# MethaneFlux.net
KiCad netlist of a schematic drawn in EAGLE
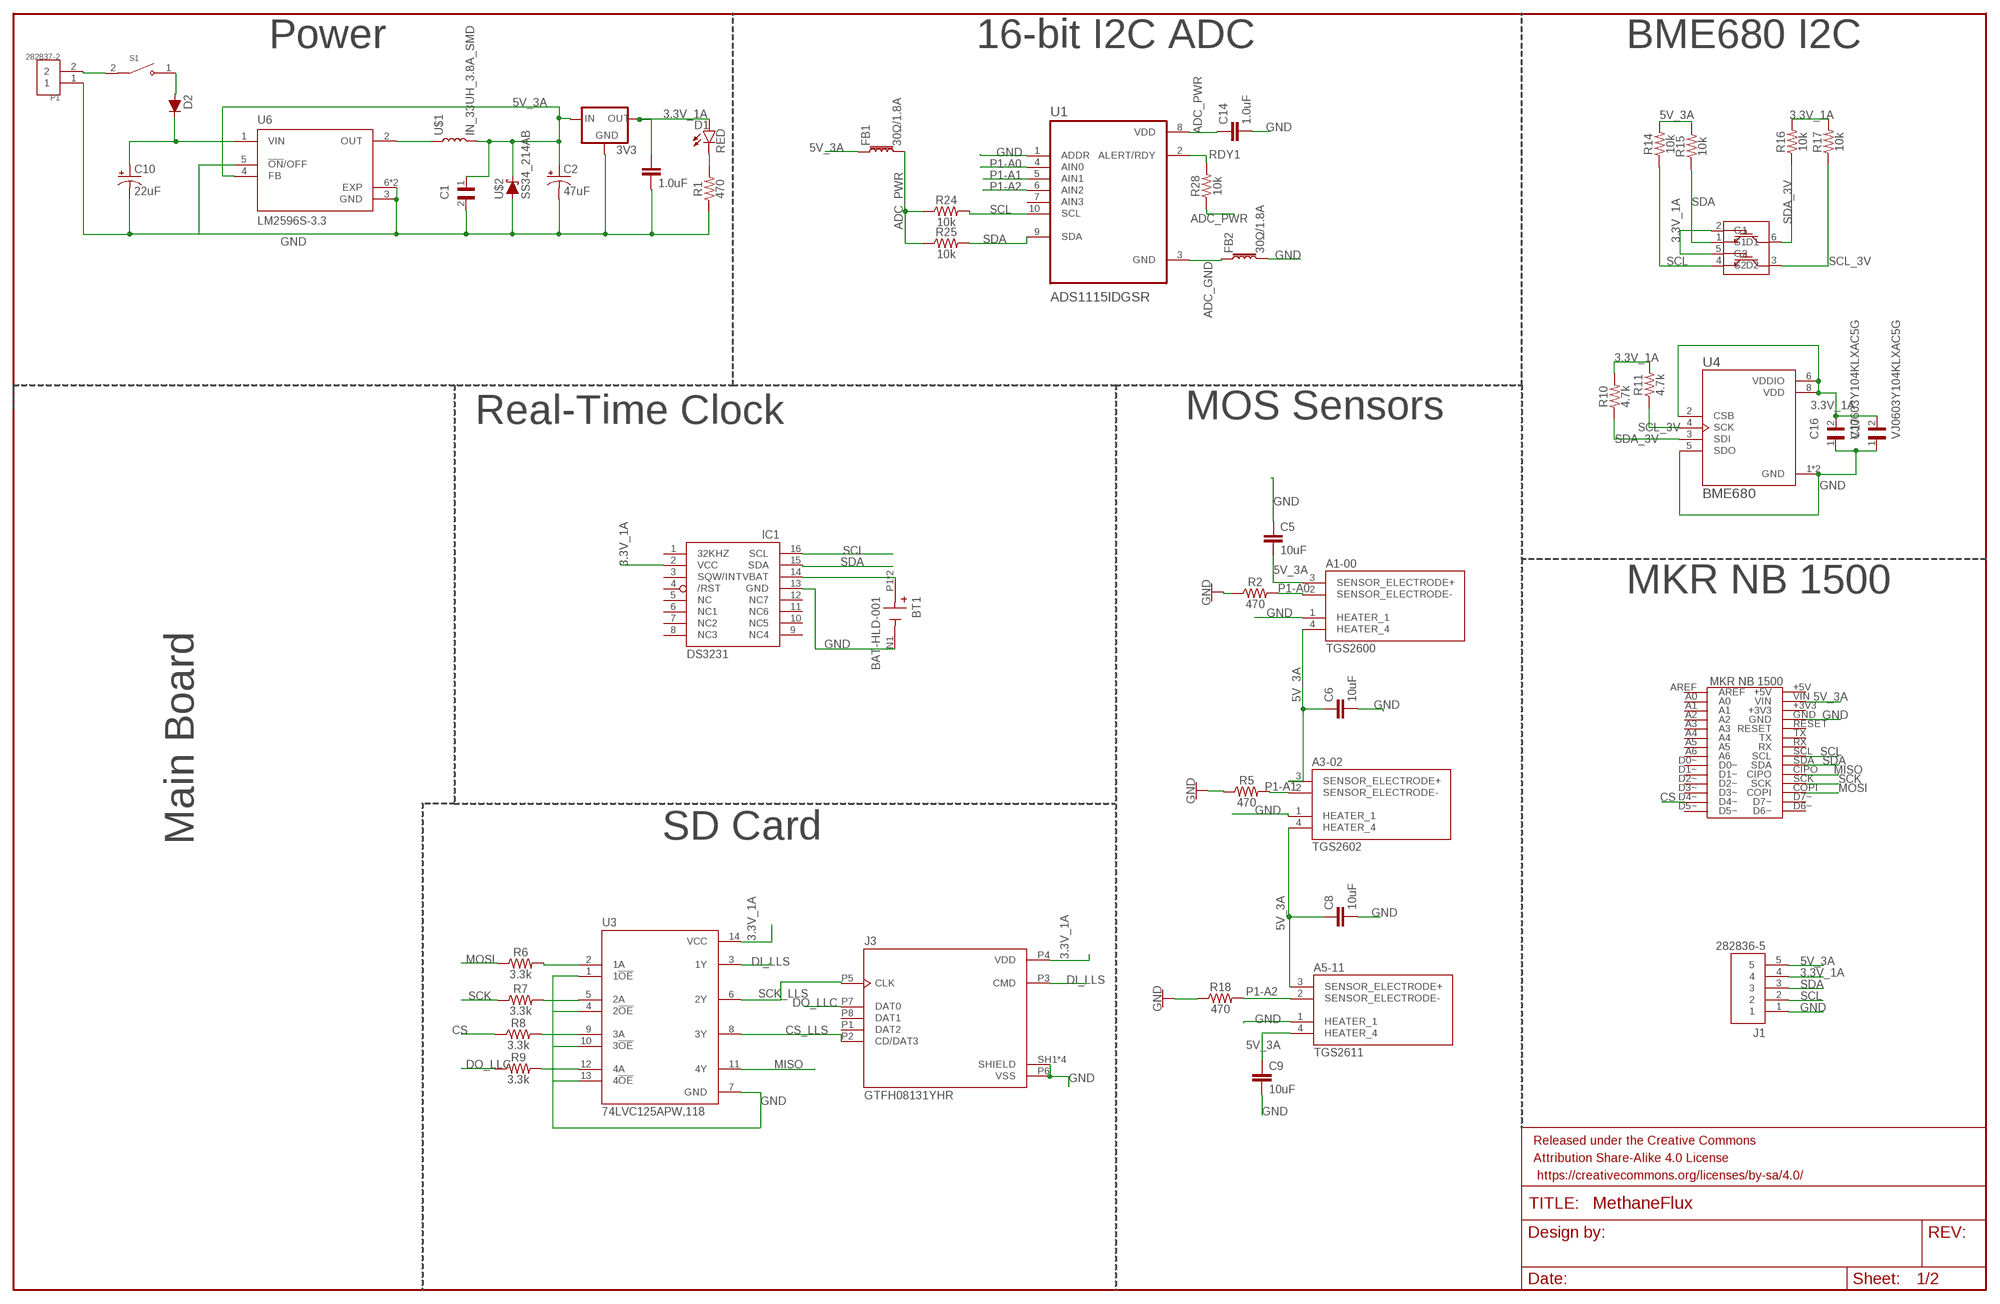
[diagram p0: schematic, sheet 1]
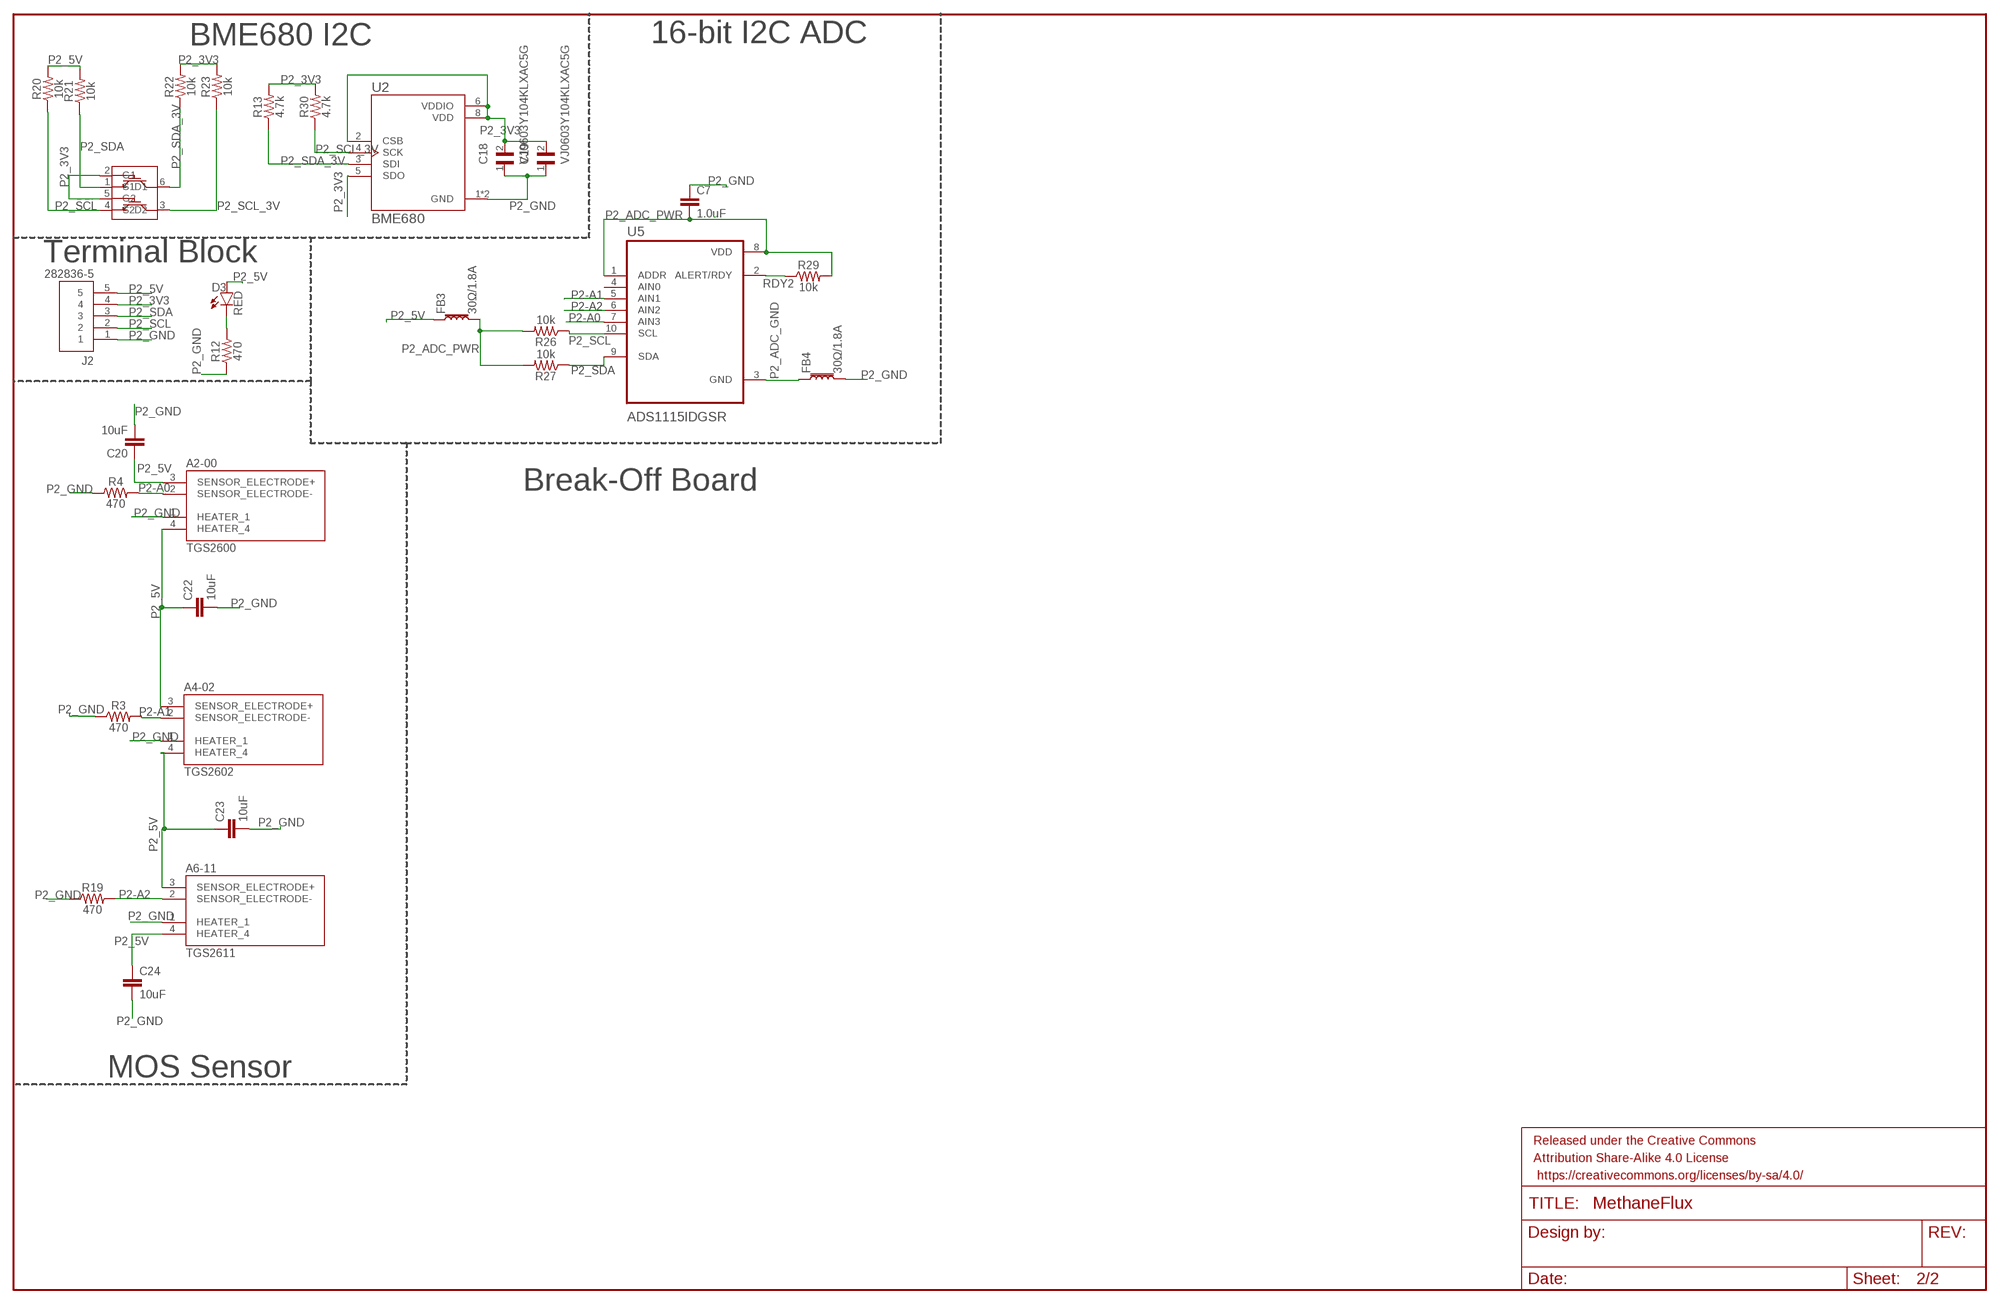
[diagram p1: schematic, sheet 2]

(export (version "E")
  (design (tool "Eeschema 10.0.6"))
  (components
    (comp (ref "3V3")
      (value "V_REG_LD1117VXXLD1117-SMD")
      (footprint "eagle-import:SOT223")
      (libsource (lib "eagle-import") (part "V_REG_LD1117VXXLD1117-SMD"))
    )
    (comp (ref "A1-00")
      (value "TGS2600")
      (footprint "eagle-import:TO255P920H830-4")
      (fields (field (name "MF") "Figaro"))
      (libsource (lib "eagle-import") (part "TGS2600"))
    )
    (comp (ref "A3-02")
      (value "TGS2602")
      (footprint "eagle-import:TGS2602")
      (libsource (lib "eagle-import") (part "TGS2602"))
    )
    (comp (ref "A5-11")
      (value "TGS2611")
      (footprint "eagle-import:TGS2611")
      (libsource (lib "eagle-import") (part "TGS2611"))
    )
    (comp (ref "BT1")
      (value "BAT-HLD-001")
      (footprint "eagle-import:BAT_BAT-HLD-001")
      (fields (field (name "MF") "Linx Technologies"))
      (libsource (lib "eagle-import") (part "BAT-HLD-001"))
    )
    (comp (ref "C1")
      (value "T491A107M004AT")
      (footprint "eagle-import:CAPC3216X110N")
      (fields (field (name "MF") "KEMET"))
      (libsource (lib "eagle-import") (part "T491A107M004AT"))
    )
    (comp (ref "C2")
      (value "47uF")
      (footprint "eagle-import:PANASONIC_D")
      (libsource (lib "eagle-import") (part "47UF-POLAR-PANASONIC_D-35V-20%"))
    )
    (comp (ref "C3")
      (value "1.0uF")
      (footprint "eagle-import:0603")
      (libsource (lib "eagle-import") (part "1.0UF-0603-16V-10%"))
    )
    (comp (ref "C5")
      (value "10uF")
      (footprint "eagle-import:0603")
      (libsource (lib "eagle-import") (part "10UF-0603-6.3V-20%"))
    )
    (comp (ref "C6")
      (value "10uF")
      (footprint "eagle-import:0603")
      (libsource (lib "eagle-import") (part "10UF-0603-6.3V-20%"))
    )
    (comp (ref "C8")
      (value "10uF")
      (footprint "eagle-import:0603")
      (libsource (lib "eagle-import") (part "10UF-0603-6.3V-20%"))
    )
    (comp (ref "C9")
      (value "10uF")
      (footprint "eagle-import:0603")
      (libsource (lib "eagle-import") (part "10UF-0603-6.3V-20%"))
    )
    (comp (ref "C10")
      (value "22uF")
      (footprint "eagle-import:PANASONIC_C")
      (libsource (lib "eagle-import") (part "22UF-POLAR-PANASONIC_C-35V-20%"))
    )
    (comp (ref "C14")
      (value "1.0uF")
      (footprint "eagle-import:0603")
      (libsource (lib "eagle-import") (part "1.0UF-0603-16V-10%"))
    )
    (comp (ref "C16")
      (value "VJ0603Y104KLXAC5G")
      (footprint "eagle-import:CAPC1608X92N")
      (fields (field (name "MF") "Vishay"))
      (libsource (lib "eagle-import") (part "VJ0603Y104KLXAC5G"))
    )
    (comp (ref "C17")
      (value "VJ0603Y104KLXAC5G")
      (footprint "eagle-import:CAPC1608X92N")
      (fields (field (name "MF") "Vishay"))
      (libsource (lib "eagle-import") (part "VJ0603Y104KLXAC5G"))
    )
    (comp (ref "D1")
      (value "RED")
      (footprint "eagle-import:LED-0603")
      (libsource (lib "eagle-import") (part "LED-RED0603"))
    )
    (comp (ref "D2")
      (value "200mA/100V/1V")
      (footprint "eagle-import:DIODE-1N4148")
      (libsource (lib "eagle-import") (part "DIODE-1N4148"))
    )
    (comp (ref "FB1")
      (value "30Ω/1.8A")
      (footprint "eagle-import:0603")
      (libsource (lib "eagle-import") (part "FERRITE_BEAD-0603"))
    )
    (comp (ref "FB2")
      (value "30Ω/1.8A")
      (footprint "eagle-import:0603")
      (libsource (lib "eagle-import") (part "FERRITE_BEAD-0603"))
    )
    (comp (ref "FRAME1")
      (value "FRAME-LEDGER")
      (footprint "eagle-import:CREATIVE_COMMONS")
      (libsource (lib "eagle-import") (part "FRAME-LEDGER"))
    )
    (comp (ref "IC1")
      (value "DS3231/SO")
      (footprint "eagle-import:SO16W")
      (fields (field (name "MF") "Analog Devices") (field (name "MP") "DS3231"))
      (libsource (lib "eagle-import") (part "DS3231/SO"))
    )
    (comp (ref "J1")
      (value "282836-5")
      (footprint "eagle-import:TE_282836-5")
      (fields (field (name "MF") "TE Connectivity"))
      (libsource (lib "eagle-import") (part "282836-5"))
    )
    (comp (ref "J3")
      (value "GTFH08131YHR")
      (footprint "eagle-import:AMPHENOL_GTFH08131YHR")
      (fields (field (name "MF") "Amphenol ICC"))
      (libsource (lib "eagle-import") (part "GTFH08131YHR"))
    )
    (comp (ref "P1")
      (value "282837-2")
      (footprint "eagle-import:TE_282837-2")
      (fields (field (name "MF") "TE Connectivity"))
      (libsource (lib "eagle-import") (part "282837-2"))
    )
    (comp (ref "R1")
      (value "470")
      (footprint "eagle-import:0603")
      (libsource (lib "eagle-import") (part "470OHM-0603-1/10W-1%"))
    )
    (comp (ref "R2")
      (value "470")
      (footprint "eagle-import:0603")
      (libsource (lib "eagle-import") (part "470OHM-0603-1/10W-1%"))
    )
    (comp (ref "R5")
      (value "470")
      (footprint "eagle-import:0603")
      (libsource (lib "eagle-import") (part "470OHM-0603-1/10W-1%"))
    )
    (comp (ref "R6")
      (value "3.3k")
      (footprint "eagle-import:0603")
      (libsource (lib "eagle-import") (part "3.3KOHM-0603-1/10W-1%"))
    )
    (comp (ref "R7")
      (value "3.3k")
      (footprint "eagle-import:0603")
      (libsource (lib "eagle-import") (part "3.3KOHM-0603-1/10W-1%"))
    )
    (comp (ref "R8")
      (value "3.3k")
      (footprint "eagle-import:0603")
      (libsource (lib "eagle-import") (part "3.3KOHM-0603-1/10W-1%"))
    )
    (comp (ref "R9")
      (value "3.3k")
      (footprint "eagle-import:0603")
      (libsource (lib "eagle-import") (part "3.3KOHM-0603-1/10W-1%"))
    )
    (comp (ref "R10")
      (value "4.7k")
      (footprint "eagle-import:0603")
      (libsource (lib "eagle-import") (part "4.7KOHM-0603-1/10W-1%"))
    )
    (comp (ref "R11")
      (value "4.7k")
      (footprint "eagle-import:0603")
      (libsource (lib "eagle-import") (part "4.7KOHM-0603-1/10W-1%"))
    )
    (comp (ref "R14")
      (value "10k")
      (footprint "eagle-import:0603")
      (libsource (lib "eagle-import") (part "10KOHM-0603-1/10W-1%"))
    )
    (comp (ref "R15")
      (value "10k")
      (footprint "eagle-import:0603")
      (libsource (lib "eagle-import") (part "10KOHM-0603-1/10W-1%"))
    )
    (comp (ref "R16")
      (value "10k")
      (footprint "eagle-import:0603")
      (libsource (lib "eagle-import") (part "10KOHM-0603-1/10W-1%"))
    )
    (comp (ref "R17")
      (value "10k")
      (footprint "eagle-import:0603")
      (libsource (lib "eagle-import") (part "10KOHM-0603-1/10W-1%"))
    )
    (comp (ref "R18")
      (value "470")
      (footprint "eagle-import:0603")
      (libsource (lib "eagle-import") (part "470OHM-0603-1/10W-1%"))
    )
    (comp (ref "R24")
      (value "10k")
      (footprint "eagle-import:0603")
      (libsource (lib "eagle-import") (part "10KOHM-0603-1/10W-1%"))
    )
    (comp (ref "R25")
      (value "10k")
      (footprint "eagle-import:0603")
      (libsource (lib "eagle-import") (part "10KOHM-0603-1/10W-1%"))
    )
    (comp (ref "R28")
      (value "10k")
      (footprint "eagle-import:0603")
      (libsource (lib "eagle-import") (part "10KOHM-0603-1/10W-1%"))
    )
    (comp (ref "S1")
      (value "RB141C1100")
      (footprint "eagle-import:SW_RB141C1100")
      (fields (field (name "MF") "E-Switch"))
      (libsource (lib "eagle-import") (part "RB141C1100"))
    )
    (comp (ref "U$1")
      (value "IN_33UH_3.8A_SMD")
      (footprint "eagle-import:INDUCTOR_4X4MM")
      (libsource (lib "eagle-import") (part "IN_33UH_3.8A_SMD"))
    )
    (comp (ref "U$2")
      (value "SS34_214AB")
      (footprint "eagle-import:SOD-323")
      (libsource (lib "eagle-import") (part "SS34_214AB"))
    )
    (comp (ref "U$3")
      (value "2N7002DW")
      (footprint "eagle-import:SOT363")
      (fields (field (name "MF") "onsemi"))
      (libsource (lib "eagle-import") (part "2N7002DW"))
    )
    (comp (ref "U$5")
      (value "MKRNB1500")
      (footprint "eagle-import:MRKNB1500")
      (libsource (lib "eagle-import") (part "MKRNB1500"))
    )
    (comp (ref "U1")
      (value "ADS1115IDGSR")
      (footprint "eagle-import:SOP50P490X110-10N")
      (fields (field (name "MF") "Texas Instruments"))
      (libsource (lib "eagle-import") (part "ADS1115IDGSR"))
    )
    (comp (ref "U3")
      (value "74LVC125APW,118")
      (footprint "eagle-import:IC_74LVC125APW,118")
      (fields (field (name "MF") "Nexperia USA Inc."))
      (libsource (lib "eagle-import") (part "74LVC125APW,118"))
    )
    (comp (ref "U4")
      (value "BME680")
      (footprint "eagle-import:PSON80P300X300X100-8N")
      (fields (field (name "MF") "Bosch Sensortec"))
      (libsource (lib "eagle-import") (part "BME680"))
    )
    (comp (ref "U6")
      (value "LM2596S-3.3")
      (footprint "eagle-import:VREG_LM2596S-3.3")
      (fields (field (name "MF") "Texas Instruments"))
      (libsource (lib "eagle-import") (part "LM2596S-3.3"))
    )
    (comp (ref "A2-00")
      (value "TGS2600")
      (footprint "eagle-import:TO255P920H830-4")
      (fields (field (name "MF") "Figaro"))
      (libsource (lib "eagle-import") (part "TGS2600"))
    )
    (comp (ref "A4-02")
      (value "TGS2602")
      (footprint "eagle-import:TGS2602")
      (libsource (lib "eagle-import") (part "TGS2602"))
    )
    (comp (ref "A6-11")
      (value "TGS2611")
      (footprint "eagle-import:TGS2611")
      (libsource (lib "eagle-import") (part "TGS2611"))
    )
    (comp (ref "C7")
      (value "1.0uF")
      (footprint "eagle-import:0603")
      (libsource (lib "eagle-import") (part "1.0UF-0603-16V-10%"))
    )
    (comp (ref "C18")
      (value "VJ0603Y104KLXAC5G")
      (footprint "eagle-import:CAPC1608X92N")
      (fields (field (name "MF") "Vishay"))
      (libsource (lib "eagle-import") (part "VJ0603Y104KLXAC5G"))
    )
    (comp (ref "C19")
      (value "VJ0603Y104KLXAC5G")
      (footprint "eagle-import:CAPC1608X92N")
      (fields (field (name "MF") "Vishay"))
      (libsource (lib "eagle-import") (part "VJ0603Y104KLXAC5G"))
    )
    (comp (ref "C20")
      (value "10uF")
      (footprint "eagle-import:0603")
      (libsource (lib "eagle-import") (part "10UF-0603-6.3V-20%"))
    )
    (comp (ref "C22")
      (value "10uF")
      (footprint "eagle-import:0603")
      (libsource (lib "eagle-import") (part "10UF-0603-6.3V-20%"))
    )
    (comp (ref "C23")
      (value "10uF")
      (footprint "eagle-import:0603")
      (libsource (lib "eagle-import") (part "10UF-0603-6.3V-20%"))
    )
    (comp (ref "C24")
      (value "10uF")
      (footprint "eagle-import:0603")
      (libsource (lib "eagle-import") (part "10UF-0603-6.3V-20%"))
    )
    (comp (ref "D3")
      (value "RED")
      (footprint "eagle-import:LED-0603")
      (libsource (lib "eagle-import") (part "LED-RED0603"))
    )
    (comp (ref "FB3")
      (value "30Ω/1.8A")
      (footprint "eagle-import:0603")
      (libsource (lib "eagle-import") (part "FERRITE_BEAD-0603"))
    )
    (comp (ref "FB4")
      (value "30Ω/1.8A")
      (footprint "eagle-import:0603")
      (libsource (lib "eagle-import") (part "FERRITE_BEAD-0603"))
    )
    (comp (ref "FRAME2")
      (value "FRAME-LEDGER")
      (footprint "eagle-import:CREATIVE_COMMONS")
      (libsource (lib "eagle-import") (part "FRAME-LEDGER"))
    )
    (comp (ref "J2")
      (value "282836-5")
      (footprint "eagle-import:TE_282836-5")
      (fields (field (name "MF") "TE Connectivity"))
      (libsource (lib "eagle-import") (part "282836-5"))
    )
    (comp (ref "R3")
      (value "470")
      (footprint "eagle-import:0603")
      (libsource (lib "eagle-import") (part "470OHM-0603-1/10W-1%"))
    )
    (comp (ref "R4")
      (value "470")
      (footprint "eagle-import:0603")
      (libsource (lib "eagle-import") (part "470OHM-0603-1/10W-1%"))
    )
    (comp (ref "R12")
      (value "470")
      (footprint "eagle-import:0603")
      (libsource (lib "eagle-import") (part "470OHM-0603-1/10W-1%"))
    )
    (comp (ref "R13")
      (value "4.7k")
      (footprint "eagle-import:0603")
      (libsource (lib "eagle-import") (part "4.7KOHM-0603-1/10W-1%"))
    )
    (comp (ref "R19")
      (value "470")
      (footprint "eagle-import:0603")
      (libsource (lib "eagle-import") (part "470OHM-0603-1/10W-1%"))
    )
    (comp (ref "R20")
      (value "10k")
      (footprint "eagle-import:0603")
      (libsource (lib "eagle-import") (part "10KOHM-0603-1/10W-1%"))
    )
    (comp (ref "R21")
      (value "10k")
      (footprint "eagle-import:0603")
      (libsource (lib "eagle-import") (part "10KOHM-0603-1/10W-1%"))
    )
    (comp (ref "R22")
      (value "10k")
      (footprint "eagle-import:0603")
      (libsource (lib "eagle-import") (part "10KOHM-0603-1/10W-1%"))
    )
    (comp (ref "R23")
      (value "10k")
      (footprint "eagle-import:0603")
      (libsource (lib "eagle-import") (part "10KOHM-0603-1/10W-1%"))
    )
    (comp (ref "R26")
      (value "10k")
      (footprint "eagle-import:0603")
      (libsource (lib "eagle-import") (part "10KOHM-0603-1/10W-1%"))
    )
    (comp (ref "R27")
      (value "10k")
      (footprint "eagle-import:0603")
      (libsource (lib "eagle-import") (part "10KOHM-0603-1/10W-1%"))
    )
    (comp (ref "R29")
      (value "10k")
      (footprint "eagle-import:0603")
      (libsource (lib "eagle-import") (part "10KOHM-0603-1/10W-1%"))
    )
    (comp (ref "R30")
      (value "4.7k")
      (footprint "eagle-import:0603")
      (libsource (lib "eagle-import") (part "4.7KOHM-0603-1/10W-1%"))
    )
    (comp (ref "U$4")
      (value "2N7002DW")
      (footprint "eagle-import:SOT363")
      (fields (field (name "MF") "onsemi"))
      (libsource (lib "eagle-import") (part "2N7002DW"))
    )
    (comp (ref "U2")
      (value "BME680")
      (footprint "eagle-import:PSON80P300X300X100-8N")
      (fields (field (name "MF") "Bosch Sensortec"))
      (libsource (lib "eagle-import") (part "BME680"))
    )
    (comp (ref "U5")
      (value "ADS1115IDGSR")
      (footprint "eagle-import:SOP50P490X110-10N")
      (fields (field (name "MF") "Texas Instruments"))
      (libsource (lib "eagle-import") (part "ADS1115IDGSR"))
    )
  )
  (nets
    (net (code "1") (name "3.3V_1A") (class "Default")
      (node (ref "3V3") (pin "2") (pinfunction "OUT_2") (pintype "passive"))
      (node (ref "C16") (pin "2") (pinfunction "2_2") (pintype "passive"))
      (node (ref "C17") (pin "2") (pinfunction "2_2") (pintype "passive"))
      (node (ref "C3") (pin "1") (pinfunction "1_1") (pintype "passive"))
      (node (ref "D1") (pin "A") (pinfunction "A_A") (pintype "passive"))
      (node (ref "IC1") (pin "2") (pinfunction "VCC_2") (pintype "power_in"))
      (node (ref "J1") (pin "4") (pinfunction "4_4") (pintype "passive"))
      (node (ref "J3") (pin "P4") (pinfunction "VDD_P4") (pintype "power_in"))
      (node (ref "R10") (pin "2") (pinfunction "2_2") (pintype "passive"))
      (node (ref "R11") (pin "2") (pinfunction "2_2") (pintype "passive"))
      (node (ref "R16") (pin "2") (pinfunction "2_2") (pintype "passive"))
      (node (ref "R17") (pin "2") (pinfunction "2_2") (pintype "passive"))
      (node (ref "U$3") (pin "2") (pinfunction "G1_2") (pintype "bidirectional"))
      (node (ref "U$3") (pin "5") (pinfunction "G2_5") (pintype "bidirectional"))
      (node (ref "U3") (pin "14") (pinfunction "VCC_14") (pintype "power_in"))
      (node (ref "U4") (pin "2") (pinfunction "CSB_2") (pintype "input"))
      (node (ref "U4") (pin "6") (pinfunction "VDDIO_6") (pintype "power_in"))
      (node (ref "U4") (pin "8") (pinfunction "VDD_8") (pintype "power_in"))
    )
    (net (code "2") (name "5V_3A") (class "Default")
      (node (ref "3V3") (pin "3") (pinfunction "IN_3") (pintype "input"))
      (node (ref "A1-00") (pin "3") (pinfunction "SENSOR_ELECTRODE+_3") (pintype "passive"))
      (node (ref "A1-00") (pin "4") (pinfunction "HEATER_4_4") (pintype "passive"))
      (node (ref "A3-02") (pin "3") (pinfunction "SENSOR_ELECTRODE+_3") (pintype "passive"))
      (node (ref "A3-02") (pin "4") (pinfunction "HEATER_4_4") (pintype "passive"))
      (node (ref "A5-11") (pin "3") (pinfunction "SENSOR_ELECTRODE+_3") (pintype "passive"))
      (node (ref "A5-11") (pin "4") (pinfunction "HEATER_4_4") (pintype "passive"))
      (node (ref "C1") (pin "1") (pinfunction "1_1") (pintype "passive"))
      (node (ref "C2") (pin "+") (pinfunction "+_+") (pintype "passive"))
      (node (ref "C5") (pin "2") (pinfunction "2_2") (pintype "passive"))
      (node (ref "C6") (pin "1") (pinfunction "1_1") (pintype "passive"))
      (node (ref "C8") (pin "1") (pinfunction "1_1") (pintype "passive"))
      (node (ref "C9") (pin "1") (pinfunction "1_1") (pintype "passive"))
      (node (ref "FB1") (pin "1") (pinfunction "1_1") (pintype "passive"))
      (node (ref "J1") (pin "5") (pinfunction "5_5") (pintype "passive"))
      (node (ref "R14") (pin "2") (pinfunction "2_2") (pintype "passive"))
      (node (ref "R15") (pin "2") (pinfunction "2_2") (pintype "passive"))
      (node (ref "U$1") (pin "P$2") (pinfunction "2_P$2") (pintype "passive"))
      (node (ref "U$2") (pin "C") (pinfunction "C_C") (pintype "passive"))
      (node (ref "U$5") (pin "VIN") (pinfunction "VIN_VIN") (pintype "bidirectional"))
      (node (ref "U6") (pin "4") (pinfunction "FB_4") (pintype "input"))
    )
    (net (code "3") (name "ADC_GND") (class "Default")
      (node (ref "FB2") (pin "1") (pinfunction "1_1") (pintype "passive"))
      (node (ref "U1") (pin "3") (pinfunction "GND_3") (pintype "power_in"))
    )
    (net (code "4") (name "ADC_PWR") (class "Default")
      (node (ref "C14") (pin "1") (pinfunction "1_1") (pintype "passive"))
      (node (ref "FB1") (pin "2") (pinfunction "2_2") (pintype "passive"))
      (node (ref "R24") (pin "1") (pinfunction "1_1") (pintype "passive"))
      (node (ref "R25") (pin "1") (pinfunction "1_1") (pintype "passive"))
      (node (ref "R28") (pin "1") (pinfunction "1_1") (pintype "passive"))
      (node (ref "U1") (pin "8") (pinfunction "VDD_8") (pintype "power_in"))
    )
    (net (code "5") (name "CS") (class "Default")
      (node (ref "R8") (pin "1") (pinfunction "1_1") (pintype "passive"))
      (node (ref "U$5") (pin "D4~") (pinfunction "D4~{}_D4~") (pintype "bidirectional"))
    )
    (net (code "6") (name "CS_LLS") (class "Default")
      (node (ref "J3") (pin "P2") (pinfunction "CD/DAT3_P2") (pintype "bidirectional"))
      (node (ref "U3") (pin "8") (pinfunction "3Y_8") (pintype "output"))
    )
    (net (code "7") (name "DI_LLS") (class "Default")
      (node (ref "J3") (pin "P3") (pinfunction "CMD_P3") (pintype "bidirectional"))
      (node (ref "U3") (pin "3") (pinfunction "1Y_3") (pintype "output"))
    )
    (net (code "8") (name "DO_LLC") (class "Default")
      (node (ref "J3") (pin "P7") (pinfunction "DAT0_P7") (pintype "bidirectional"))
      (node (ref "R9") (pin "1") (pinfunction "1_1") (pintype "passive"))
    )
    (net (code "9") (name "GND") (class "Default")
      (node (ref "3V3") (pin "1") (pinfunction "GND_1") (pintype "input"))
      (node (ref "A1-00") (pin "1") (pinfunction "HEATER_1_1") (pintype "passive"))
      (node (ref "A3-02") (pin "1") (pinfunction "HEATER_1_1") (pintype "passive"))
      (node (ref "A5-11") (pin "1") (pinfunction "HEATER_1_1") (pintype "passive"))
      (node (ref "BT1") (pin "N1") (pinfunction "-_N1") (pintype "passive"))
      (node (ref "C1") (pin "2") (pinfunction "2_2") (pintype "passive"))
      (node (ref "C10") (pin "-") (pinfunction "-_-") (pintype "passive"))
      (node (ref "C14") (pin "2") (pinfunction "2_2") (pintype "passive"))
      (node (ref "C16") (pin "1") (pinfunction "1_1") (pintype "passive"))
      (node (ref "C17") (pin "1") (pinfunction "1_1") (pintype "passive"))
      (node (ref "C2") (pin "-") (pinfunction "-_-") (pintype "passive"))
      (node (ref "C3") (pin "2") (pinfunction "2_2") (pintype "passive"))
      (node (ref "C5") (pin "1") (pinfunction "1_1") (pintype "passive"))
      (node (ref "C6") (pin "2") (pinfunction "2_2") (pintype "passive"))
      (node (ref "C8") (pin "2") (pinfunction "2_2") (pintype "passive"))
      (node (ref "C9") (pin "2") (pinfunction "2_2") (pintype "passive"))
      (node (ref "FB2") (pin "2") (pinfunction "2_2") (pintype "passive"))
      (node (ref "IC1") (pin "13") (pinfunction "GND_13") (pintype "power_in"))
      (node (ref "J1") (pin "1") (pinfunction "1_1") (pintype "passive"))
      (node (ref "J3") (pin "P6") (pinfunction "VSS_P6") (pintype "power_in"))
      (node (ref "J3") (pin "SH1") (pinfunction "SHIELD_SH1") (pintype "power_in"))
      (node (ref "J3") (pin "SH2") (pinfunction "SHIELD_SH2") (pintype "power_in"))
      (node (ref "J3") (pin "SH3") (pinfunction "SHIELD_SH3") (pintype "power_in"))
      (node (ref "J3") (pin "SH4") (pinfunction "SHIELD_SH4") (pintype "power_in"))
      (node (ref "P1") (pin "1") (pinfunction "1_1") (pintype "passive"))
      (node (ref "R1") (pin "1") (pinfunction "1_1") (pintype "passive"))
      (node (ref "R18") (pin "1") (pinfunction "1_1") (pintype "passive"))
      (node (ref "R2") (pin "1") (pinfunction "1_1") (pintype "passive"))
      (node (ref "R5") (pin "1") (pinfunction "1_1") (pintype "passive"))
      (node (ref "U$2") (pin "A") (pinfunction "A_A") (pintype "passive"))
      (node (ref "U$5") (pin "GND") (pinfunction "GND_GND") (pintype "bidirectional"))
      (node (ref "U1") (pin "1") (pinfunction "ADDR_1") (pintype "input"))
      (node (ref "U3") (pin "1") (pinfunction "1~{OE}_1") (pintype "input"))
      (node (ref "U3") (pin "10") (pinfunction "3~{OE}_10") (pintype "input"))
      (node (ref "U3") (pin "13") (pinfunction "4~{OE}_13") (pintype "input"))
      (node (ref "U3") (pin "4") (pinfunction "2~{OE}_4") (pintype "input"))
      (node (ref "U3") (pin "7") (pinfunction "GND_7") (pintype "power_in"))
      (node (ref "U4") (pin "1") (pinfunction "GND_1") (pintype "power_in"))
      (node (ref "U4") (pin "5") (pinfunction "SDO_5") (pintype "bidirectional"))
      (node (ref "U4") (pin "7") (pinfunction "GND_7") (pintype "power_in"))
      (node (ref "U6") (pin "3") (pinfunction "GND_3") (pintype "power_in"))
      (node (ref "U6") (pin "5") (pinfunction "~{ON}/OFF_5") (pintype "input"))
      (node (ref "U6") (pin "6") (pinfunction "EXP_6") (pintype "power_in"))
      (node (ref "U6") (pin "7") (pinfunction "EXP_7") (pintype "power_in"))
    )
    (net (code "10") (name "MISO") (class "Default")
      (node (ref "U$5") (pin "CIPO") (pinfunction "CIPO_CIPO") (pintype "bidirectional"))
      (node (ref "U3") (pin "11") (pinfunction "4Y_11") (pintype "output"))
    )
    (net (code "11") (name "MOSI") (class "Default")
      (node (ref "R6") (pin "1") (pinfunction "1_1") (pintype "passive"))
      (node (ref "U$5") (pin "COPI") (pinfunction "COPI_COPI") (pintype "bidirectional"))
    )
    (net (code "12") (name "Net-(D1-PadC)") (class "Default")
      (node (ref "D1") (pin "C") (pinfunction "C_C") (pintype "passive"))
      (node (ref "R1") (pin "2") (pinfunction "2_2") (pintype "passive"))
    )
    (net (code "13") (name "Net-(D2-PadA)") (class "Default")
      (node (ref "D2") (pin "A") (pinfunction "A_A") (pintype "passive"))
      (node (ref "S1") (pin "1") (pinfunction "1_1") (pintype "passive"))
    )
    (net (code "14") (name "Net-(D3-PadC)") (class "Default")
      (node (ref "D3") (pin "C") (pinfunction "C_C") (pintype "passive"))
      (node (ref "R12") (pin "2") (pinfunction "2_2") (pintype "passive"))
    )
    (net (code "15") (name "Net-(IC1-VBAT)") (class "Default")
      (node (ref "BT1") (pin "P1") (pinfunction "+_P1") (pintype "passive"))
      (node (ref "BT1") (pin "P2") (pinfunction "+_P2") (pintype "passive"))
      (node (ref "IC1") (pin "14") (pinfunction "VBAT_14") (pintype "power_in"))
    )
    (net (code "16") (name "Net-(P1-Pad2)") (class "Default")
      (node (ref "P1") (pin "2") (pinfunction "2_2") (pintype "passive"))
      (node (ref "S1") (pin "2") (pinfunction "2_2") (pintype "passive"))
    )
    (net (code "17") (name "Net-(U$1-1)") (class "Default")
      (node (ref "U$1") (pin "P$1") (pinfunction "1_P$1") (pintype "passive"))
      (node (ref "U6") (pin "2") (pinfunction "OUT_2") (pintype "output"))
    )
    (net (code "18") (name "Net-(U3-1A)") (class "Default")
      (node (ref "R6") (pin "2") (pinfunction "2_2") (pintype "passive"))
      (node (ref "U3") (pin "2") (pinfunction "1A_2") (pintype "input"))
    )
    (net (code "19") (name "Net-(U3-2A)") (class "Default")
      (node (ref "R7") (pin "2") (pinfunction "2_2") (pintype "passive"))
      (node (ref "U3") (pin "5") (pinfunction "2A_5") (pintype "input"))
    )
    (net (code "20") (name "Net-(U3-3A)") (class "Default")
      (node (ref "R8") (pin "2") (pinfunction "2_2") (pintype "passive"))
      (node (ref "U3") (pin "9") (pinfunction "3A_9") (pintype "input"))
    )
    (net (code "21") (name "Net-(U3-4A)") (class "Default")
      (node (ref "R9") (pin "2") (pinfunction "2_2") (pintype "passive"))
      (node (ref "U3") (pin "12") (pinfunction "4A_12") (pintype "input"))
    )
    (net (code "22") (name "Net-(U6-VIN)") (class "Default")
      (node (ref "C10") (pin "+") (pinfunction "+_+") (pintype "passive"))
      (node (ref "D2") (pin "C") (pinfunction "C_C") (pintype "passive"))
      (node (ref "U6") (pin "1") (pinfunction "VIN_1") (pintype "input"))
    )
    (net (code "23") (name "P1-A0") (class "Default")
      (node (ref "A1-00") (pin "2") (pinfunction "SENSOR_ELECTRODE-_2") (pintype "passive"))
      (node (ref "R2") (pin "2") (pinfunction "2_2") (pintype "passive"))
      (node (ref "U1") (pin "4") (pinfunction "AIN0_4") (pintype "input"))
    )
    (net (code "24") (name "P1-A1") (class "Default")
      (node (ref "A3-02") (pin "2") (pinfunction "SENSOR_ELECTRODE-_2") (pintype "passive"))
      (node (ref "R5") (pin "2") (pinfunction "2_2") (pintype "passive"))
      (node (ref "U1") (pin "5") (pinfunction "AIN1_5") (pintype "input"))
    )
    (net (code "25") (name "P1-A2") (class "Default")
      (node (ref "A5-11") (pin "2") (pinfunction "SENSOR_ELECTRODE-_2") (pintype "passive"))
      (node (ref "R18") (pin "2") (pinfunction "2_2") (pintype "passive"))
      (node (ref "U1") (pin "6") (pinfunction "AIN2_6") (pintype "input"))
    )
    (net (code "26") (name "P2-A0") (class "Default")
      (node (ref "A2-00") (pin "2") (pinfunction "SENSOR_ELECTRODE-_2") (pintype "passive"))
      (node (ref "R4") (pin "2") (pinfunction "2_2") (pintype "passive"))
      (node (ref "U5") (pin "7") (pinfunction "AIN3_7") (pintype "input"))
    )
    (net (code "27") (name "P2-A1") (class "Default")
      (node (ref "A4-02") (pin "2") (pinfunction "SENSOR_ELECTRODE-_2") (pintype "passive"))
      (node (ref "R3") (pin "2") (pinfunction "2_2") (pintype "passive"))
      (node (ref "U5") (pin "5") (pinfunction "AIN1_5") (pintype "input"))
    )
    (net (code "28") (name "P2-A2") (class "Default")
      (node (ref "A6-11") (pin "2") (pinfunction "SENSOR_ELECTRODE-_2") (pintype "passive"))
      (node (ref "R19") (pin "2") (pinfunction "2_2") (pintype "passive"))
      (node (ref "U5") (pin "6") (pinfunction "AIN2_6") (pintype "input"))
    )
    (net (code "29") (name "P2_3V3") (class "Default")
      (node (ref "C18") (pin "2") (pinfunction "2_2") (pintype "passive"))
      (node (ref "C19") (pin "2") (pinfunction "2_2") (pintype "passive"))
      (node (ref "J2") (pin "4") (pinfunction "4_4") (pintype "passive"))
      (node (ref "R13") (pin "2") (pinfunction "2_2") (pintype "passive"))
      (node (ref "R22") (pin "2") (pinfunction "2_2") (pintype "passive"))
      (node (ref "R23") (pin "2") (pinfunction "2_2") (pintype "passive"))
      (node (ref "R30") (pin "2") (pinfunction "2_2") (pintype "passive"))
      (node (ref "U$4") (pin "2") (pinfunction "G1_2") (pintype "bidirectional"))
      (node (ref "U$4") (pin "5") (pinfunction "G2_5") (pintype "bidirectional"))
      (node (ref "U2") (pin "2") (pinfunction "CSB_2") (pintype "input"))
      (node (ref "U2") (pin "5") (pinfunction "SDO_5") (pintype "bidirectional"))
      (node (ref "U2") (pin "6") (pinfunction "VDDIO_6") (pintype "power_in"))
      (node (ref "U2") (pin "8") (pinfunction "VDD_8") (pintype "power_in"))
    )
    (net (code "30") (name "P2_5V") (class "Default")
      (node (ref "A2-00") (pin "3") (pinfunction "SENSOR_ELECTRODE+_3") (pintype "passive"))
      (node (ref "A2-00") (pin "4") (pinfunction "HEATER_4_4") (pintype "passive"))
      (node (ref "A4-02") (pin "3") (pinfunction "SENSOR_ELECTRODE+_3") (pintype "passive"))
      (node (ref "A4-02") (pin "4") (pinfunction "HEATER_4_4") (pintype "passive"))
      (node (ref "A6-11") (pin "3") (pinfunction "SENSOR_ELECTRODE+_3") (pintype "passive"))
      (node (ref "A6-11") (pin "4") (pinfunction "HEATER_4_4") (pintype "passive"))
      (node (ref "C20") (pin "1") (pinfunction "1_1") (pintype "passive"))
      (node (ref "C22") (pin "1") (pinfunction "1_1") (pintype "passive"))
      (node (ref "C23") (pin "1") (pinfunction "1_1") (pintype "passive"))
      (node (ref "C24") (pin "1") (pinfunction "1_1") (pintype "passive"))
      (node (ref "D3") (pin "A") (pinfunction "A_A") (pintype "passive"))
      (node (ref "FB3") (pin "1") (pinfunction "1_1") (pintype "passive"))
      (node (ref "J2") (pin "5") (pinfunction "5_5") (pintype "passive"))
      (node (ref "R20") (pin "2") (pinfunction "2_2") (pintype "passive"))
      (node (ref "R21") (pin "2") (pinfunction "2_2") (pintype "passive"))
    )
    (net (code "31") (name "P2_ADC_GND") (class "Default")
      (node (ref "FB4") (pin "1") (pinfunction "1_1") (pintype "passive"))
      (node (ref "U5") (pin "3") (pinfunction "GND_3") (pintype "power_in"))
    )
    (net (code "32") (name "P2_ADC_PWR") (class "Default")
      (node (ref "C7") (pin "2") (pinfunction "2_2") (pintype "passive"))
      (node (ref "FB3") (pin "2") (pinfunction "2_2") (pintype "passive"))
      (node (ref "R26") (pin "2") (pinfunction "2_2") (pintype "passive"))
      (node (ref "R27") (pin "2") (pinfunction "2_2") (pintype "passive"))
      (node (ref "R29") (pin "2") (pinfunction "2_2") (pintype "passive"))
      (node (ref "U5") (pin "1") (pinfunction "ADDR_1") (pintype "input"))
      (node (ref "U5") (pin "8") (pinfunction "VDD_8") (pintype "power_in"))
    )
    (net (code "33") (name "P2_GND") (class "Default")
      (node (ref "A2-00") (pin "1") (pinfunction "HEATER_1_1") (pintype "passive"))
      (node (ref "A4-02") (pin "1") (pinfunction "HEATER_1_1") (pintype "passive"))
      (node (ref "A6-11") (pin "1") (pinfunction "HEATER_1_1") (pintype "passive"))
      (node (ref "C18") (pin "1") (pinfunction "1_1") (pintype "passive"))
      (node (ref "C19") (pin "1") (pinfunction "1_1") (pintype "passive"))
      (node (ref "C20") (pin "2") (pinfunction "2_2") (pintype "passive"))
      (node (ref "C22") (pin "2") (pinfunction "2_2") (pintype "passive"))
      (node (ref "C23") (pin "2") (pinfunction "2_2") (pintype "passive"))
      (node (ref "C24") (pin "2") (pinfunction "2_2") (pintype "passive"))
      (node (ref "C7") (pin "1") (pinfunction "1_1") (pintype "passive"))
      (node (ref "FB4") (pin "2") (pinfunction "2_2") (pintype "passive"))
      (node (ref "J2") (pin "1") (pinfunction "1_1") (pintype "passive"))
      (node (ref "R12") (pin "1") (pinfunction "1_1") (pintype "passive"))
      (node (ref "R19") (pin "1") (pinfunction "1_1") (pintype "passive"))
      (node (ref "R3") (pin "1") (pinfunction "1_1") (pintype "passive"))
      (node (ref "R4") (pin "1") (pinfunction "1_1") (pintype "passive"))
      (node (ref "U2") (pin "1") (pinfunction "GND_1") (pintype "power_in"))
      (node (ref "U2") (pin "7") (pinfunction "GND_7") (pintype "power_in"))
    )
    (net (code "34") (name "P2_SCL") (class "Default")
      (node (ref "J2") (pin "2") (pinfunction "2_2") (pintype "passive"))
      (node (ref "R20") (pin "1") (pinfunction "1_1") (pintype "passive"))
      (node (ref "R26") (pin "1") (pinfunction "1_1") (pintype "passive"))
      (node (ref "U$4") (pin "4") (pinfunction "S2_4") (pintype "bidirectional"))
      (node (ref "U5") (pin "10") (pinfunction "SCL_10") (pintype "input"))
    )
    (net (code "35") (name "P2_SCL_3V") (class "Default")
      (node (ref "R23") (pin "1") (pinfunction "1_1") (pintype "passive"))
      (node (ref "R30") (pin "1") (pinfunction "1_1") (pintype "passive"))
      (node (ref "U$4") (pin "3") (pinfunction "D2_3") (pintype "bidirectional"))
      (node (ref "U2") (pin "4") (pinfunction "SCK_4") (pintype "input"))
    )
    (net (code "36") (name "P2_SDA") (class "Default")
      (node (ref "J2") (pin "3") (pinfunction "3_3") (pintype "passive"))
      (node (ref "R21") (pin "1") (pinfunction "1_1") (pintype "passive"))
      (node (ref "R27") (pin "1") (pinfunction "1_1") (pintype "passive"))
      (node (ref "U$4") (pin "1") (pinfunction "S1_1") (pintype "bidirectional"))
      (node (ref "U5") (pin "9") (pinfunction "SDA_9") (pintype "bidirectional"))
    )
    (net (code "37") (name "P2_SDA_3V") (class "Default")
      (node (ref "R13") (pin "1") (pinfunction "1_1") (pintype "passive"))
      (node (ref "R22") (pin "1") (pinfunction "1_1") (pintype "passive"))
      (node (ref "U$4") (pin "6") (pinfunction "D1_6") (pintype "bidirectional"))
      (node (ref "U2") (pin "3") (pinfunction "SDI_3") (pintype "bidirectional"))
    )
    (net (code "38") (name "RDY1") (class "Default")
      (node (ref "R28") (pin "2") (pinfunction "2_2") (pintype "passive"))
      (node (ref "U1") (pin "2") (pinfunction "ALERT/RDY_2") (pintype "output"))
    )
    (net (code "39") (name "RDY2") (class "Default")
      (node (ref "R29") (pin "1") (pinfunction "1_1") (pintype "passive"))
      (node (ref "U5") (pin "2") (pinfunction "ALERT/RDY_2") (pintype "output"))
    )
    (net (code "40") (name "SCK") (class "Default")
      (node (ref "R7") (pin "1") (pinfunction "1_1") (pintype "passive"))
      (node (ref "U$5") (pin "SCK") (pinfunction "SCK_SCK") (pintype "bidirectional"))
    )
    (net (code "41") (name "SCK_LLS") (class "Default")
      (node (ref "J3") (pin "P5") (pinfunction "CLK_P5") (pintype "bidirectional"))
      (node (ref "U3") (pin "6") (pinfunction "2Y_6") (pintype "output"))
    )
    (net (code "42") (name "SCL") (class "Default")
      (node (ref "IC1") (pin "16") (pinfunction "SCL_16") (pintype "bidirectional"))
      (node (ref "J1") (pin "2") (pinfunction "2_2") (pintype "passive"))
      (node (ref "R14") (pin "1") (pinfunction "1_1") (pintype "passive"))
      (node (ref "R24") (pin "2") (pinfunction "2_2") (pintype "passive"))
      (node (ref "U$3") (pin "4") (pinfunction "S2_4") (pintype "bidirectional"))
      (node (ref "U$5") (pin "SCL") (pinfunction "SCL_SCL") (pintype "bidirectional"))
      (node (ref "U1") (pin "10") (pinfunction "SCL_10") (pintype "input"))
    )
    (net (code "43") (name "SCL_3V") (class "Default")
      (node (ref "R11") (pin "1") (pinfunction "1_1") (pintype "passive"))
      (node (ref "R17") (pin "1") (pinfunction "1_1") (pintype "passive"))
      (node (ref "U$3") (pin "3") (pinfunction "D2_3") (pintype "bidirectional"))
      (node (ref "U4") (pin "4") (pinfunction "SCK_4") (pintype "input"))
    )
    (net (code "44") (name "SDA") (class "Default")
      (node (ref "IC1") (pin "15") (pinfunction "SDA_15") (pintype "bidirectional"))
      (node (ref "J1") (pin "3") (pinfunction "3_3") (pintype "passive"))
      (node (ref "R15") (pin "1") (pinfunction "1_1") (pintype "passive"))
      (node (ref "R25") (pin "2") (pinfunction "2_2") (pintype "passive"))
      (node (ref "U$3") (pin "1") (pinfunction "S1_1") (pintype "bidirectional"))
      (node (ref "U$5") (pin "SDA") (pinfunction "SDA_SDA") (pintype "bidirectional"))
      (node (ref "U1") (pin "9") (pinfunction "SDA_9") (pintype "bidirectional"))
    )
    (net (code "45") (name "SDA_3V") (class "Default")
      (node (ref "R10") (pin "1") (pinfunction "1_1") (pintype "passive"))
      (node (ref "R16") (pin "1") (pinfunction "1_1") (pintype "passive"))
      (node (ref "U$3") (pin "6") (pinfunction "D1_6") (pintype "bidirectional"))
      (node (ref "U4") (pin "3") (pinfunction "SDI_3") (pintype "bidirectional"))
    )
    (net (code "46") (name "unconnected-(IC1-32KHZ-Pad1)") (class "Default")
      (node (ref "IC1") (pin "1") (pinfunction "32KHZ_1") (pintype "output"))
    )
    (net (code "47") (name "unconnected-(IC1-NC-Pad5)") (class "Default")
      (node (ref "IC1") (pin "5") (pinfunction "NC_5") (pintype "no_connect"))
    )
    (net (code "48") (name "unconnected-(IC1-NC1-Pad6)") (class "Default")
      (node (ref "IC1") (pin "6") (pinfunction "NC1_6") (pintype "no_connect"))
    )
    (net (code "49") (name "unconnected-(IC1-NC2-Pad7)") (class "Default")
      (node (ref "IC1") (pin "7") (pinfunction "NC2_7") (pintype "no_connect"))
    )
    (net (code "50") (name "unconnected-(IC1-NC3-Pad8)") (class "Default")
      (node (ref "IC1") (pin "8") (pinfunction "NC3_8") (pintype "no_connect"))
    )
    (net (code "51") (name "unconnected-(IC1-NC4-Pad9)") (class "Default")
      (node (ref "IC1") (pin "9") (pinfunction "NC4_9") (pintype "no_connect"))
    )
    (net (code "52") (name "unconnected-(IC1-NC5-Pad10)") (class "Default")
      (node (ref "IC1") (pin "10") (pinfunction "NC5_10") (pintype "no_connect"))
    )
    (net (code "53") (name "unconnected-(IC1-NC6-Pad11)") (class "Default")
      (node (ref "IC1") (pin "11") (pinfunction "NC6_11") (pintype "no_connect"))
    )
    (net (code "54") (name "unconnected-(IC1-NC7-Pad12)") (class "Default")
      (node (ref "IC1") (pin "12") (pinfunction "NC7_12") (pintype "no_connect"))
    )
    (net (code "55") (name "unconnected-(IC1-SQW{slash}INT-Pad3)") (class "Default")
      (node (ref "IC1") (pin "3") (pinfunction "SQW/INT_3") (pintype "output"))
    )
    (net (code "56") (name "unconnected-(IC1-{slash}RST-Pad4)") (class "Default")
      (node (ref "IC1") (pin "4") (pinfunction "/RST_4") (pintype "passive"))
    )
    (net (code "57") (name "unconnected-(J3-DAT1-PadP8)") (class "Default")
      (node (ref "J3") (pin "P8") (pinfunction "DAT1_P8") (pintype "bidirectional"))
    )
    (net (code "58") (name "unconnected-(J3-DAT2-PadP1)") (class "Default")
      (node (ref "J3") (pin "P1") (pinfunction "DAT2_P1") (pintype "bidirectional"))
    )
    (net (code "59") (name "unconnected-(U$5-D0~{}-PadD0~)") (class "Default")
      (node (ref "U$5") (pin "D0~") (pinfunction "D0~{}_D0~") (pintype "bidirectional"))
    )
    (net (code "60") (name "unconnected-(U$5-D1~{}-PadD1~)") (class "Default")
      (node (ref "U$5") (pin "D1~") (pinfunction "D1~{}_D1~") (pintype "bidirectional"))
    )
    (net (code "61") (name "unconnected-(U$5-D2~{}-PadD2~)") (class "Default")
      (node (ref "U$5") (pin "D2~") (pinfunction "D2~{}_D2~") (pintype "bidirectional"))
    )
    (net (code "62") (name "unconnected-(U$5-D3~{}-PadD3~)") (class "Default")
      (node (ref "U$5") (pin "D3~") (pinfunction "D3~{}_D3~") (pintype "bidirectional"))
    )
    (net (code "63") (name "unconnected-(U$5-D5~{}-PadD5~)") (class "Default")
      (node (ref "U$5") (pin "D5~") (pinfunction "D5~{}_D5~") (pintype "bidirectional"))
    )
    (net (code "64") (name "unconnected-(U$5-D6~{}-PadD6~)") (class "Default")
      (node (ref "U$5") (pin "D6~") (pinfunction "D6~{}_D6~") (pintype "bidirectional"))
    )
    (net (code "65") (name "unconnected-(U$5-D7~{}-PadD7~)") (class "Default")
      (node (ref "U$5") (pin "D7~") (pinfunction "D7~{}_D7~") (pintype "bidirectional"))
    )
    (net (code "66") (name "unconnected-(U$5-Pad+3V3)") (class "Default")
      (node (ref "U$5") (pin "+3V3") (pinfunction "+3V3_+3V3") (pintype "bidirectional"))
    )
    (net (code "67") (name "unconnected-(U$5-Pad+5V)") (class "Default")
      (node (ref "U$5") (pin "+5V") (pinfunction "+5V_+5V") (pintype "bidirectional"))
    )
    (net (code "68") (name "unconnected-(U$5-PadA0)") (class "Default")
      (node (ref "U$5") (pin "A0") (pinfunction "A0_A0") (pintype "bidirectional"))
    )
    (net (code "69") (name "unconnected-(U$5-PadA1)") (class "Default")
      (node (ref "U$5") (pin "A1") (pinfunction "A1_A1") (pintype "bidirectional"))
    )
    (net (code "70") (name "unconnected-(U$5-PadA2)") (class "Default")
      (node (ref "U$5") (pin "A2") (pinfunction "A2_A2") (pintype "bidirectional"))
    )
    (net (code "71") (name "unconnected-(U$5-PadA3)") (class "Default")
      (node (ref "U$5") (pin "A3") (pinfunction "A3_A3") (pintype "bidirectional"))
    )
    (net (code "72") (name "unconnected-(U$5-PadA4)") (class "Default")
      (node (ref "U$5") (pin "A4") (pinfunction "A4_A4") (pintype "bidirectional"))
    )
    (net (code "73") (name "unconnected-(U$5-PadA5)") (class "Default")
      (node (ref "U$5") (pin "A5") (pinfunction "A5_A5") (pintype "bidirectional"))
    )
    (net (code "74") (name "unconnected-(U$5-PadA6)") (class "Default")
      (node (ref "U$5") (pin "A6") (pinfunction "A6_A6") (pintype "bidirectional"))
    )
    (net (code "75") (name "unconnected-(U$5-PadAREF)") (class "Default")
      (node (ref "U$5") (pin "AREF") (pinfunction "AREF_AREF") (pintype "bidirectional"))
    )
    (net (code "76") (name "unconnected-(U$5-PadRESET)") (class "Default")
      (node (ref "U$5") (pin "RESET") (pinfunction "RESET_RESET") (pintype "bidirectional"))
    )
    (net (code "77") (name "unconnected-(U$5-PadRX)") (class "Default")
      (node (ref "U$5") (pin "RX") (pinfunction "RX_RX") (pintype "bidirectional"))
    )
    (net (code "78") (name "unconnected-(U$5-PadTX)") (class "Default")
      (node (ref "U$5") (pin "TX") (pinfunction "TX_TX") (pintype "bidirectional"))
    )
    (net (code "79") (name "unconnected-(U1-AIN3-Pad7)") (class "Default")
      (node (ref "U1") (pin "7") (pinfunction "AIN3_7") (pintype "input"))
    )
    (net (code "80") (name "unconnected-(U5-AIN0-Pad4)") (class "Default")
      (node (ref "U5") (pin "4") (pinfunction "AIN0_4") (pintype "input"))
    )
  )
)
